# SIM800L.net
KiCad netlist of a schematic drawn in Altium Designer
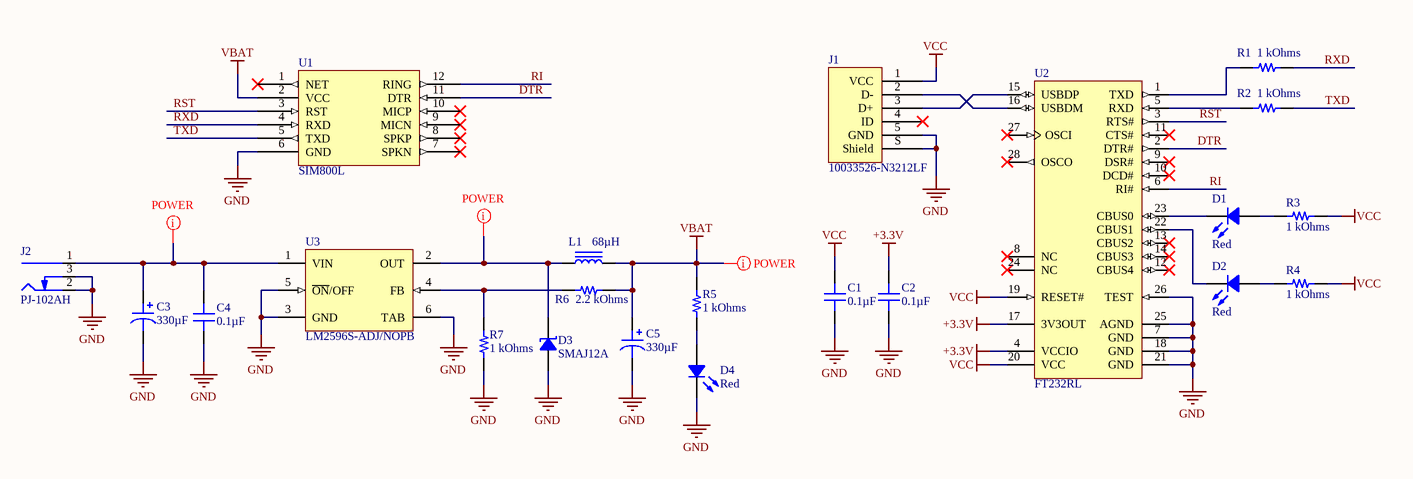
[diagram p0: SIM800L.SchDoc]

(export (version "E")
  (design (tool "Eeschema 10.0.6"))
  (components
    (comp (ref "C1")
      (value "0.1µF")
      (footprint "CAP 0805_2012")
      (description "CAP CER 0805 10% X8R 50V 100NF")
      (fields (field (name "PART NUMBER") "AC0805KKX8R9BB104") (field (name "MANUFACTURER") "Yageo"))
      (libsource (lib "Altium Database Library V2 Local") (part "Capacitor"))
    )
    (comp (ref "C2")
      (value "0.1µF")
      (footprint "CAP 0805_2012")
      (description "CAP CER 0805 10% X8R 50V 100NF")
      (fields (field (name "PART NUMBER") "AC0805KKX8R9BB104") (field (name "MANUFACTURER") "Yageo"))
      (libsource (lib "Altium Database Library V2 Local") (part "Capacitor"))
    )
    (comp (ref "C3")
      (value "330µF")
      (footprint "CAP AL TH D8 L3.5 H12.5")
      (description "CAP ALUM 330UF 20% 25V RADIAL")
      (fields
        (field (name "PART NUMBER") "ECA-1EHG331")
        (field (name "MANUFACTURER") "Panasonic Electronic Components")
      )
      (libsource (lib "Altium Database Library V2 Local") (part "Polarised Capacitor"))
    )
    (comp (ref "C4")
      (value "0.1µF")
      (footprint "CAP 0805_2012")
      (description "CAP CER 0805 10% X8R 50V 100NF")
      (fields (field (name "PART NUMBER") "AC0805KKX8R9BB104") (field (name "MANUFACTURER") "Yageo"))
      (libsource (lib "Altium Database Library V2 Local") (part "Capacitor"))
    )
    (comp (ref "C5")
      (value "330µF")
      (footprint "CAP AL TH D8 L3.5 H12.5")
      (description "CAP ALUM 330UF 20% 25V RADIAL")
      (fields
        (field (name "PART NUMBER") "ECA-1EHG331")
        (field (name "MANUFACTURER") "Panasonic Electronic Components")
      )
      (libsource (lib "Altium Database Library V2 Local") (part "Polarised Capacitor"))
    )
    (comp (ref "D1")
      (value "Red")
      (footprint "LED 1206_3216 RED")
      (description "LED RED CLEAR 2SMD")
      (fields
        (field (name "PART NUMBER") "EASR3216RA0")
        (field (name "MANUFACTURER") "Everlight Electronics Co Ltd")
      )
      (libsource (lib "Altium Database Library V2 Local") (part "LED"))
    )
    (comp (ref "D2")
      (value "Red")
      (footprint "LED 1206_3216 RED")
      (description "LED RED CLEAR 2SMD")
      (fields
        (field (name "PART NUMBER") "EASR3216RA0")
        (field (name "MANUFACTURER") "Everlight Electronics Co Ltd")
      )
      (libsource (lib "Altium Database Library V2 Local") (part "LED"))
    )
    (comp (ref "D3")
      (value "SMAJ12A")
      (footprint "DO214AC SMA")
      (description "TVS DIODE 12V 19.9V DO214AC")
      (fields (field (name "MANUFACTURER") "Littelfuse Inc."))
      (libsource (lib "Altium Database Library V2 Local") (part "DIODE TVS UNI"))
    )
    (comp (ref "D4")
      (value "Red")
      (footprint "LED 1206_3216 RED")
      (description "LED RED CLEAR 2SMD")
      (fields
        (field (name "PART NUMBER") "EASR3216RA0")
        (field (name "MANUFACTURER") "Everlight Electronics Co Ltd")
      )
      (libsource (lib "Altium Database Library V2 Local") (part "LED"))
    )
    (comp (ref "J1")
      (value "10033526-N3212LF")
      (footprint "FCI USB 10033526-N3212LF")
      (description "CONN RCPT MINI USB B 5POS SMD RA")
      (fields (field (name "MANUFACTURER") "Amphenol ICC (FCI)"))
      (libsource (lib "Altium Database Library V2 Local") (part "USB 2.0 Type B Micro"))
    )
    (comp (ref "J2")
      (value "PJ-102AH")
      (footprint "CUI PJ-102AH")
      (description "CONN PWR JACK 2X5.5MM SOLDER")
      (fields (field (name "MANUFACTURER") "CUI Devices"))
      (libsource (lib "Altium Database Library V2 Local") (part "Barrel Connector"))
    )
    (comp (ref "L1")
      (value "68µH")
      (footprint "TDK SLF12575")
      (description "FIXED IND 68UH 2A 77.8 MOHM SMD")
      (fields
        (field (name "PART NUMBER") "SLF12575T-680M2R0-PF")
        (field (name "MANUFACTURER") "TDK Corporation")
      )
      (libsource (lib "Altium Database Library V2 Local") (part "Inductor"))
    )
    (comp (ref "R1")
      (value "1 kOhms")
      (footprint "RES 0805_2012")
      (description "RES SMD 1K OHM 5% 1/8W 0805")
      (fields
        (field (name "PART NUMBER") "ERJ-6GEYJ102V")
        (field (name "MANUFACTURER") "Panasonic Electronic Components")
      )
      (libsource (lib "Altium Database Library V2 Local") (part "Resistor"))
    )
    (comp (ref "R2")
      (value "1 kOhms")
      (footprint "RES 0805_2012")
      (description "RES SMD 1K OHM 5% 1/8W 0805")
      (fields
        (field (name "PART NUMBER") "ERJ-6GEYJ102V")
        (field (name "MANUFACTURER") "Panasonic Electronic Components")
      )
      (libsource (lib "Altium Database Library V2 Local") (part "Resistor"))
    )
    (comp (ref "R3")
      (value "1 kOhms")
      (footprint "RES 0805_2012")
      (description "RES SMD 1K OHM 5% 1/8W 0805")
      (fields
        (field (name "PART NUMBER") "ERJ-6GEYJ102V")
        (field (name "MANUFACTURER") "Panasonic Electronic Components")
      )
      (libsource (lib "Altium Database Library V2 Local") (part "Resistor"))
    )
    (comp (ref "R4")
      (value "1 kOhms")
      (footprint "RES 0805_2012")
      (description "RES SMD 1K OHM 5% 1/8W 0805")
      (fields
        (field (name "PART NUMBER") "ERJ-6GEYJ102V")
        (field (name "MANUFACTURER") "Panasonic Electronic Components")
      )
      (libsource (lib "Altium Database Library V2 Local") (part "Resistor"))
    )
    (comp (ref "R5")
      (value "1 kOhms")
      (footprint "RES 0805_2012")
      (description "RES SMD 1K OHM 5% 1/8W 0805")
      (fields
        (field (name "PART NUMBER") "ERJ-6GEYJ102V")
        (field (name "MANUFACTURER") "Panasonic Electronic Components")
      )
      (libsource (lib "Altium Database Library V2 Local") (part "Resistor"))
    )
    (comp (ref "R6")
      (value "2.2 kOhms")
      (footprint "RES 0805_2012")
      (description "RES SMD 2.2K OHM 5% 1/2W 0805")
      (fields
        (field (name "PART NUMBER") "ERJ-P06J222V")
        (field (name "MANUFACTURER") "Panasonic Electronic Components")
      )
      (libsource (lib "Altium Database Library V2 Local") (part "Resistor"))
    )
    (comp (ref "R7")
      (value "1 kOhms")
      (footprint "RES 0805_2012")
      (description "RES SMD 1K OHM 5% 1/8W 0805")
      (fields
        (field (name "PART NUMBER") "ERJ-6GEYJ102V")
        (field (name "MANUFACTURER") "Panasonic Electronic Components")
      )
      (libsource (lib "Altium Database Library V2 Local") (part "Resistor"))
    )
    (comp (ref "U1") (value "SIM800L") (footprint "SIM800L") (libsource (lib "SIM800L") (part "SIM800L")))
    (comp (ref "U2")
      (value "FT232RL")
      (footprint "FTDI-SSOP-28_M")
      (description "IC USB FS SERIAL UART 28-SSOP")
      (fields (field (name "MANUFACTURER") "FTDI"))
      (libsource (lib "FT232RL") (part "CMP-2000-05029-1"))
    )
    (comp (ref "U3")
      (value "LM2596S-ADJ/NOPB")
      (footprint "TO263-5")
      (description "SIMPLE SWITCHER® Power Converter 150 KHz 3A Step-Down Voltage Regulator, 5-pin TO-263, Pb-Free")
      (fields (field (name "MANUFACTURER") "Texas Instruments"))
      (libsource (lib "LM2596") (part "LM2596S-ADJ/NOPB"))
    )
  )
  (nets
    (net (code "1") (name "+3.3V") (class "Default")
      (node (ref "C2") (pin "2") (pinfunction "2_2") (pintype "passive"))
      (node (ref "U2") (pin "17") (pinfunction "3V3OUT_17") (pintype "power_in"))
      (node (ref "U2") (pin "4") (pinfunction "VCCIO_4") (pintype "power_in"))
    )
    (net (code "2") (name "/DTR") (class "Default")
      (node (ref "U1") (pin "11") (pinfunction "DTR_11") (pintype "input"))
      (node (ref "U2") (pin "2") (pinfunction "DTR#_2") (pintype "output"))
    )
    (net (code "3") (name "/RI") (class "Default")
      (node (ref "U1") (pin "12") (pinfunction "RING_12") (pintype "output"))
      (node (ref "U2") (pin "6") (pinfunction "RI#_6") (pintype "input"))
    )
    (net (code "4") (name "/RST") (class "Default")
      (node (ref "U1") (pin "3") (pinfunction "RST_3") (pintype "input"))
      (node (ref "U2") (pin "3") (pinfunction "RTS#_3") (pintype "output"))
    )
    (net (code "5") (name "/RXD") (class "Default")
      (node (ref "R1") (pin "1") (pinfunction "1_1") (pintype "passive"))
      (node (ref "U1") (pin "4") (pinfunction "RXD_4") (pintype "input"))
    )
    (net (code "6") (name "/TXD") (class "Default")
      (node (ref "R2") (pin "1") (pinfunction "1_1") (pintype "passive"))
      (node (ref "U1") (pin "5") (pinfunction "TXD_5") (pintype "output"))
    )
    (net (code "7") (name "GND") (class "Default")
      (node (ref "C1") (pin "1") (pinfunction "1_1") (pintype "passive"))
      (node (ref "C2") (pin "1") (pinfunction "1_1") (pintype "passive"))
      (node (ref "C3") (pin "2") (pinfunction "2_2") (pintype "passive"))
      (node (ref "C4") (pin "1") (pinfunction "1_1") (pintype "passive"))
      (node (ref "C5") (pin "2") (pinfunction "2_2") (pintype "passive"))
      (node (ref "D3") (pin "1") (pinfunction "1_1") (pintype "passive"))
      (node (ref "D4") (pin "2") (pinfunction "2_2") (pintype "passive"))
      (node (ref "J1") (pin "5") (pinfunction "GND_5") (pintype "passive"))
      (node (ref "J1") (pin "S") (pinfunction "Shield_S") (pintype "passive"))
      (node (ref "J2") (pin "2") (pinfunction "Outer_2") (pintype "passive"))
      (node (ref "J2") (pin "3") (pinfunction "SW_3") (pintype "passive"))
      (node (ref "R7") (pin "1") (pinfunction "1_1") (pintype "passive"))
      (node (ref "U1") (pin "6") (pinfunction "GND_6") (pintype "power_in"))
      (node (ref "U2") (pin "18") (pinfunction "GND_18") (pintype "power_in"))
      (node (ref "U2") (pin "21") (pinfunction "GND_21") (pintype "power_in"))
      (node (ref "U2") (pin "25") (pinfunction "AGND_25") (pintype "power_in"))
      (node (ref "U2") (pin "26") (pinfunction "TEST_26") (pintype "input"))
      (node (ref "U2") (pin "7") (pinfunction "GND_7") (pintype "power_in"))
      (node (ref "U3") (pin "3") (pinfunction "GND_3") (pintype "power_in"))
      (node (ref "U3") (pin "5") (pinfunction "~{ON}/OFF_5") (pintype "input"))
      (node (ref "U3") (pin "6") (pinfunction "TAB_6") (pintype "power_in"))
    )
    (net (code "8") (name "Net-(D1-Pad1)") (class "Default")
      (node (ref "D1") (pin "1") (pinfunction "1_1") (pintype "passive"))
      (node (ref "R3") (pin "2") (pinfunction "2_2") (pintype "passive"))
    )
    (net (code "9") (name "Net-(D2-Pad1)") (class "Default")
      (node (ref "D2") (pin "1") (pinfunction "1_1") (pintype "passive"))
      (node (ref "R4") (pin "2") (pinfunction "2_2") (pintype "passive"))
    )
    (net (code "10") (name "Net-(D4-Pad1)") (class "Default")
      (node (ref "D4") (pin "1") (pinfunction "1_1") (pintype "passive"))
      (node (ref "R5") (pin "1") (pinfunction "1_1") (pintype "passive"))
    )
    (net (code "11") (name "Net-(J1-D+)") (class "Default")
      (node (ref "J1") (pin "3") (pinfunction "D+_3") (pintype "passive"))
      (node (ref "U2") (pin "15") (pinfunction "USBDP_15") (pintype "bidirectional"))
    )
    (net (code "12") (name "Net-(J1-D-)") (class "Default")
      (node (ref "J1") (pin "2") (pinfunction "D-_2") (pintype "passive"))
      (node (ref "U2") (pin "16") (pinfunction "USBDM_16") (pintype "bidirectional"))
    )
    (net (code "13") (name "Net-(J2-Centre)") (class "Default")
      (node (ref "C3") (pin "1") (pinfunction "1_1") (pintype "passive"))
      (node (ref "C4") (pin "2") (pinfunction "2_2") (pintype "passive"))
      (node (ref "J2") (pin "1") (pinfunction "Centre_1") (pintype "passive"))
      (node (ref "U3") (pin "1") (pinfunction "VIN_1") (pintype "power_in"))
    )
    (net (code "14") (name "Net-(U2-CBUS0)") (class "Default")
      (node (ref "D1") (pin "2") (pinfunction "2_2") (pintype "passive"))
      (node (ref "U2") (pin "23") (pinfunction "CBUS0_23") (pintype "bidirectional"))
    )
    (net (code "15") (name "Net-(U2-CBUS1)") (class "Default")
      (node (ref "D2") (pin "2") (pinfunction "2_2") (pintype "passive"))
      (node (ref "U2") (pin "22") (pinfunction "CBUS1_22") (pintype "bidirectional"))
    )
    (net (code "16") (name "Net-(U2-RXD)") (class "Default")
      (node (ref "R2") (pin "2") (pinfunction "2_2") (pintype "passive"))
      (node (ref "U2") (pin "5") (pinfunction "RXD_5") (pintype "input"))
    )
    (net (code "17") (name "Net-(U2-TXD)") (class "Default")
      (node (ref "R1") (pin "2") (pinfunction "2_2") (pintype "passive"))
      (node (ref "U2") (pin "1") (pinfunction "TXD_1") (pintype "output"))
    )
    (net (code "18") (name "Net-(U3-FB)") (class "Default")
      (node (ref "R6") (pin "1") (pinfunction "1_1") (pintype "passive"))
      (node (ref "R7") (pin "2") (pinfunction "2_2") (pintype "passive"))
      (node (ref "U3") (pin "4") (pinfunction "FB_4") (pintype "input"))
    )
    (net (code "19") (name "Net-(U3-OUT)") (class "Default")
      (node (ref "D3") (pin "2") (pinfunction "2_2") (pintype "passive"))
      (node (ref "L1") (pin "1") (pinfunction "1_1") (pintype "passive"))
      (node (ref "U3") (pin "2") (pinfunction "OUT_2") (pintype "power_in"))
    )
    (net (code "20") (name "VBAT") (class "Default")
      (node (ref "C5") (pin "1") (pinfunction "1_1") (pintype "passive"))
      (node (ref "L1") (pin "2") (pinfunction "2_2") (pintype "passive"))
      (node (ref "R5") (pin "2") (pinfunction "2_2") (pintype "passive"))
      (node (ref "R6") (pin "2") (pinfunction "2_2") (pintype "passive"))
      (node (ref "U1") (pin "2") (pinfunction "VCC_2") (pintype "power_in"))
    )
    (net (code "21") (name "VCC") (class "Default")
      (node (ref "C1") (pin "2") (pinfunction "2_2") (pintype "passive"))
      (node (ref "J1") (pin "1") (pinfunction "VCC_1") (pintype "passive"))
      (node (ref "R3") (pin "1") (pinfunction "1_1") (pintype "passive"))
      (node (ref "R4") (pin "1") (pinfunction "1_1") (pintype "passive"))
      (node (ref "U2") (pin "19") (pinfunction "RESET#_19") (pintype "input"))
      (node (ref "U2") (pin "20") (pinfunction "VCC_20") (pintype "power_in"))
    )
    (net (code "22") (name "unconnected-(J1-ID-Pad4)") (class "Default")
      (node (ref "J1") (pin "4") (pinfunction "ID_4") (pintype "passive+no_connect"))
    )
    (net (code "23") (name "unconnected-(U1-MICN-Pad9)") (class "Default")
      (node (ref "U1") (pin "9") (pinfunction "MICN_9") (pintype "input+no_connect"))
    )
    (net (code "24") (name "unconnected-(U1-MICP-Pad10)") (class "Default")
      (node (ref "U1") (pin "10") (pinfunction "MICP_10") (pintype "input+no_connect"))
    )
    (net (code "25") (name "unconnected-(U1-NET-Pad1)") (class "Default")
      (node (ref "U1") (pin "1") (pinfunction "NET_1") (pintype "output+no_connect"))
    )
    (net (code "26") (name "unconnected-(U1-SPKN-Pad7)") (class "Default")
      (node (ref "U1") (pin "7") (pinfunction "SPKN_7") (pintype "output+no_connect"))
    )
    (net (code "27") (name "unconnected-(U1-SPKP-Pad8)") (class "Default")
      (node (ref "U1") (pin "8") (pinfunction "SPKP_8") (pintype "output+no_connect"))
    )
    (net (code "28") (name "unconnected-(U2-CBUS2-Pad13)") (class "Default")
      (node (ref "U2") (pin "13") (pinfunction "CBUS2_13") (pintype "bidirectional+no_connect"))
    )
    (net (code "29") (name "unconnected-(U2-CBUS3-Pad14)") (class "Default")
      (node (ref "U2") (pin "14") (pinfunction "CBUS3_14") (pintype "bidirectional+no_connect"))
    )
    (net (code "30") (name "unconnected-(U2-CBUS4-Pad12)") (class "Default")
      (node (ref "U2") (pin "12") (pinfunction "CBUS4_12") (pintype "bidirectional+no_connect"))
    )
    (net (code "31") (name "unconnected-(U2-CTS#-Pad11)") (class "Default")
      (node (ref "U2") (pin "11") (pinfunction "CTS#_11") (pintype "input+no_connect"))
    )
    (net (code "32") (name "unconnected-(U2-DCD#-Pad10)") (class "Default")
      (node (ref "U2") (pin "10") (pinfunction "DCD#_10") (pintype "input+no_connect"))
    )
    (net (code "33") (name "unconnected-(U2-DSR#-Pad9)") (class "Default")
      (node (ref "U2") (pin "9") (pinfunction "DSR#_9") (pintype "input+no_connect"))
    )
    (net (code "34") (name "unconnected-(U2-NC-Pad8)") (class "Default")
      (node (ref "U2") (pin "8") (pinfunction "NC_8") (pintype "passive+no_connect"))
    )
    (net (code "35") (name "unconnected-(U2-NC-Pad24)") (class "Default")
      (node (ref "U2") (pin "24") (pinfunction "NC_24") (pintype "passive+no_connect"))
    )
    (net (code "36") (name "unconnected-(U2-OSCI-Pad27)") (class "Default")
      (node (ref "U2") (pin "27") (pinfunction "OSCI_27") (pintype "input+no_connect"))
    )
    (net (code "37") (name "unconnected-(U2-OSCO-Pad28)") (class "Default")
      (node (ref "U2") (pin "28") (pinfunction "OSCO_28") (pintype "output+no_connect"))
    )
  )
)
